# SensorPCB.net
KiCad netlist of a schematic drawn in EAGLE
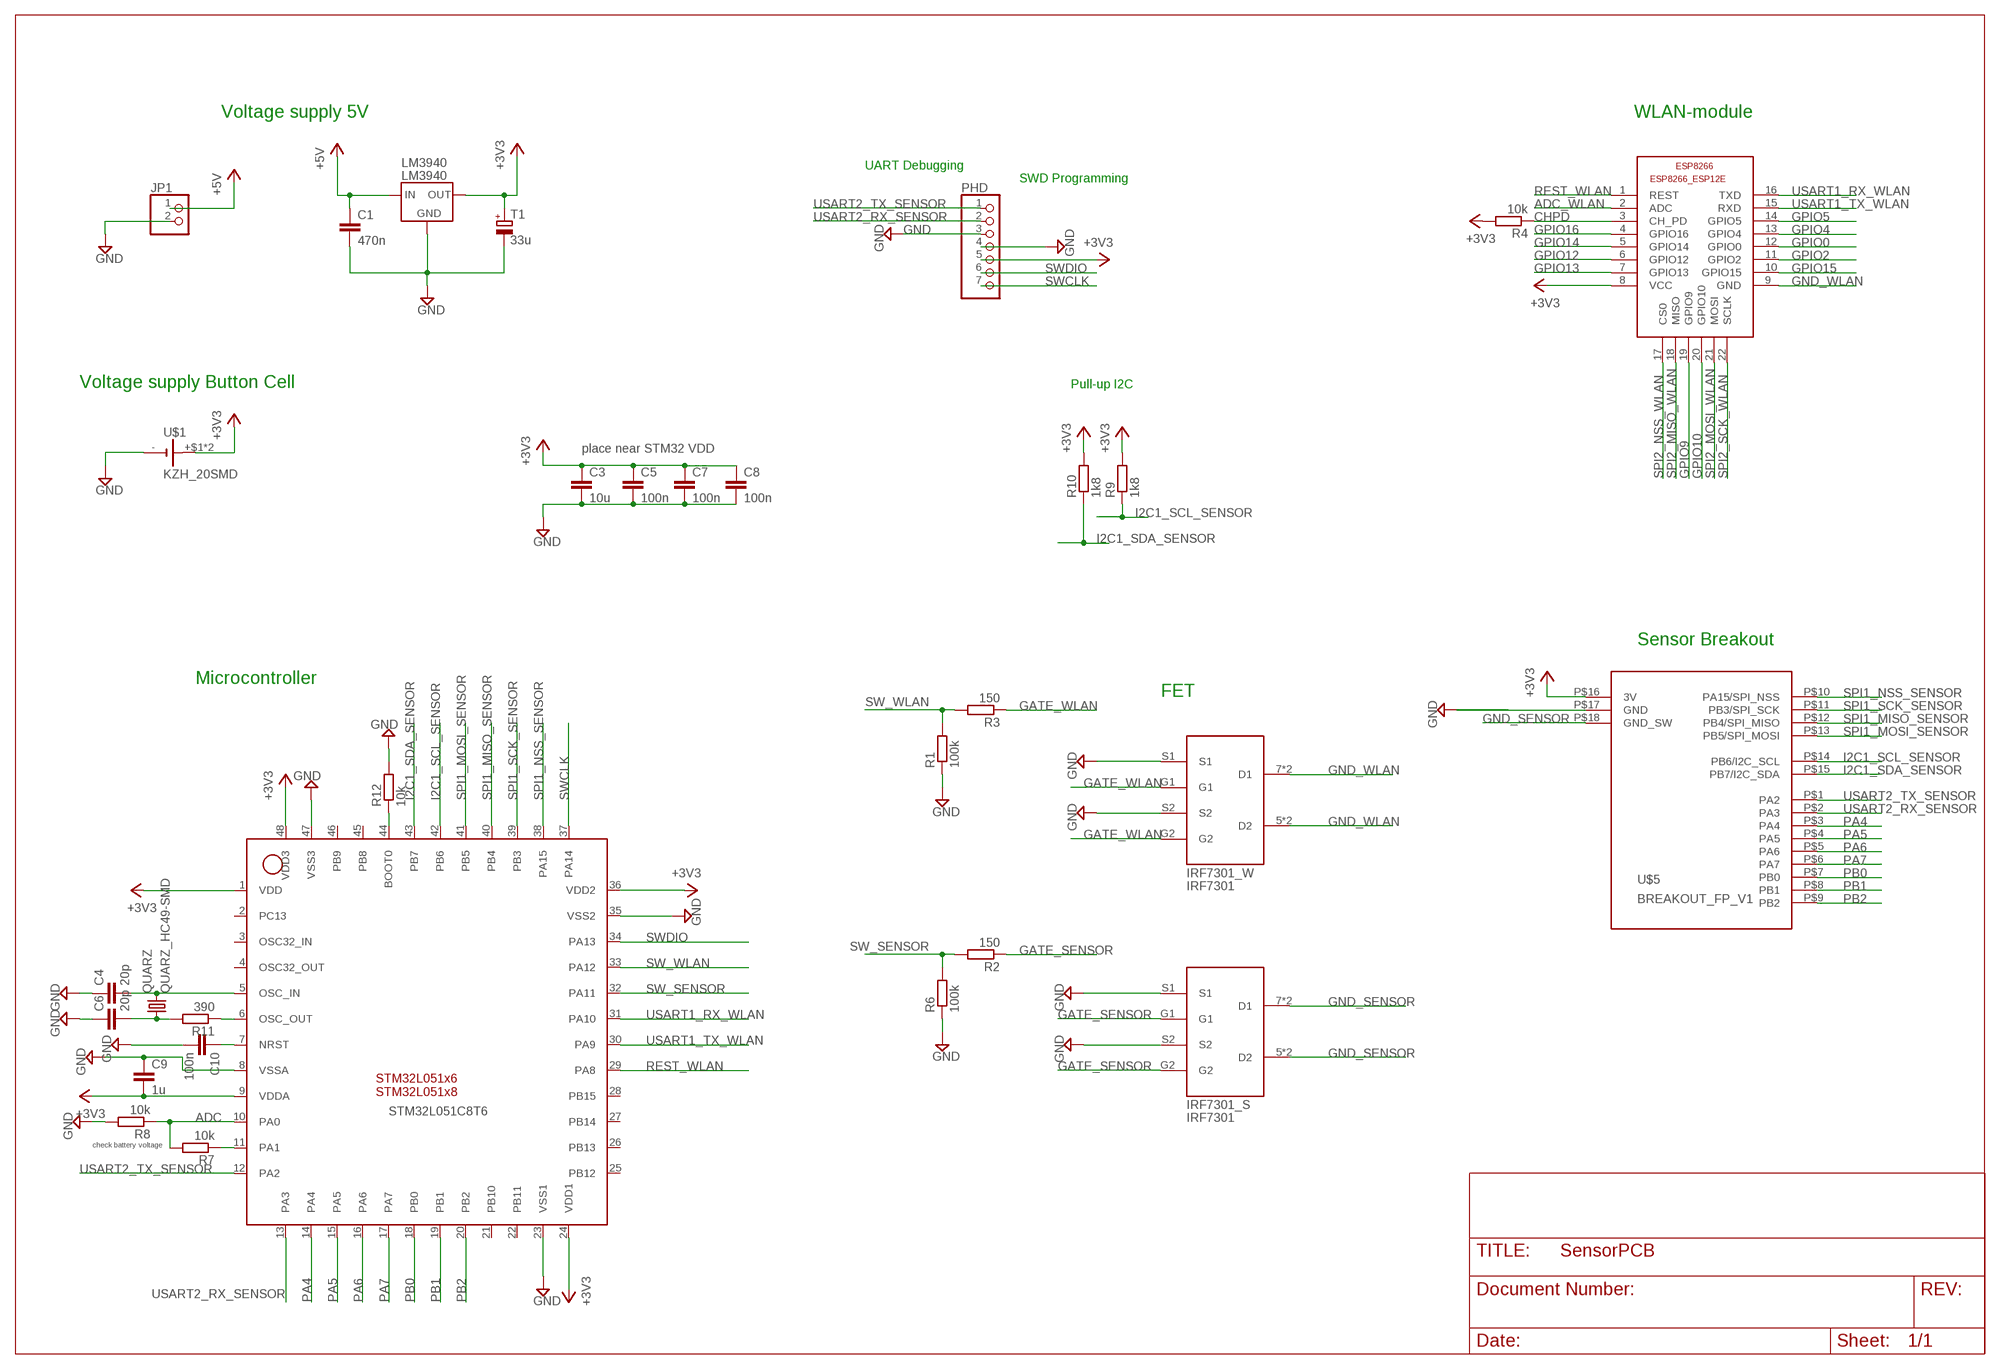
[diagram p0: schematic, sheet 1]

(export (version "E")
  (design (tool "Eeschema 10.0.6"))
  (components
    (comp (ref "C1")
      (value "470n")
      (footprint "eagle-import:C0805")
      (libsource (lib "eagle-import") (part "C-EUC0805"))
    )
    (comp (ref "C3")
      (value "10u")
      (footprint "eagle-import:C0805")
      (libsource (lib "eagle-import") (part "C-EUC0805"))
    )
    (comp (ref "C4")
      (value "20p")
      (footprint "eagle-import:C0805")
      (libsource (lib "eagle-import") (part "C-EUC0805"))
    )
    (comp (ref "C5")
      (value "100n")
      (footprint "eagle-import:C0805")
      (libsource (lib "eagle-import") (part "C-EUC0805"))
    )
    (comp (ref "C6")
      (value "20p")
      (footprint "eagle-import:C0805")
      (libsource (lib "eagle-import") (part "C-EUC0805"))
    )
    (comp (ref "C7")
      (value "100n")
      (footprint "eagle-import:C0805")
      (libsource (lib "eagle-import") (part "C-EUC0805"))
    )
    (comp (ref "C8")
      (value "100n")
      (footprint "eagle-import:C0805")
      (libsource (lib "eagle-import") (part "C-EUC0805"))
    )
    (comp (ref "C9")
      (value "1u")
      (footprint "eagle-import:C0805")
      (libsource (lib "eagle-import") (part "C-EUC0805"))
    )
    (comp (ref "C10")
      (value "100n")
      (footprint "eagle-import:C0805")
      (libsource (lib "eagle-import") (part "C-EUC0805"))
    )
    (comp (ref "ESP8266")
      (value "ESP8266-12EESP8266-ESP12E")
      (footprint "eagle-import:ESP8266-ESP12E")
      (libsource (lib "eagle-import") (part "ESP8266-12EESP8266-ESP12E"))
    )
    (comp (ref "IRF7301_S")
      (value "IRF7301")
      (footprint "eagle-import:IRF7301_PACK_SO8")
      (libsource (lib "eagle-import") (part "IRF7301"))
    )
    (comp (ref "IRF7301_W")
      (value "IRF7301")
      (footprint "eagle-import:IRF7301_PACK_SO8")
      (libsource (lib "eagle-import") (part "IRF7301"))
    )
    (comp (ref "JP1")
      (value "PINHD-1X2_2.54-SMD")
      (footprint "eagle-import:1X02SMD")
      (libsource (lib "eagle-import") (part "PINHD-1X2_2.54-SMD"))
    )
    (comp (ref "LM3940")
      (value "LM3940")
      (footprint "eagle-import:LM3940_PACK")
      (libsource (lib "eagle-import") (part "LM3940"))
    )
    (comp (ref "PHD")
      (value "PINHD-1X7_2.54-SMD")
      (footprint "eagle-import:1X07SMD")
      (libsource (lib "eagle-import") (part "PINHD-1X7_2.54-SMD"))
    )
    (comp (ref "QUARZ")
      (value "QUARZ_HC49-SMD")
      (footprint "eagle-import:HC49-SMD")
      (libsource (lib "eagle-import") (part "QUARZ_HC49-SMD"))
    )
    (comp (ref "R1")
      (value "100k")
      (footprint "eagle-import:R0805")
      (libsource (lib "eagle-import") (part "R-EU_R0805"))
    )
    (comp (ref "R2")
      (value "150")
      (footprint "eagle-import:R0805")
      (libsource (lib "eagle-import") (part "R-EU_R0805"))
    )
    (comp (ref "R3")
      (value "150")
      (footprint "eagle-import:R0805")
      (libsource (lib "eagle-import") (part "R-EU_R0805"))
    )
    (comp (ref "R4")
      (value "10k")
      (footprint "eagle-import:R0805")
      (libsource (lib "eagle-import") (part "R-EU_R0805"))
    )
    (comp (ref "R6")
      (value "100k")
      (footprint "eagle-import:R0805")
      (libsource (lib "eagle-import") (part "R-EU_R0805"))
    )
    (comp (ref "R7")
      (value "10k")
      (footprint "eagle-import:R0805")
      (libsource (lib "eagle-import") (part "R-EU_R0805"))
    )
    (comp (ref "R8")
      (value "10k")
      (footprint "eagle-import:R0805")
      (libsource (lib "eagle-import") (part "R-EU_R0805"))
    )
    (comp (ref "R9")
      (value "1k8")
      (footprint "eagle-import:R0805")
      (libsource (lib "eagle-import") (part "R-EU_R0805"))
    )
    (comp (ref "R10")
      (value "1k8")
      (footprint "eagle-import:R0805")
      (libsource (lib "eagle-import") (part "R-EU_R0805"))
    )
    (comp (ref "R11")
      (value "390")
      (footprint "eagle-import:R0805")
      (libsource (lib "eagle-import") (part "R-EU_R0805"))
    )
    (comp (ref "R12")
      (value "10k")
      (footprint "eagle-import:R0805")
      (libsource (lib "eagle-import") (part "R-EU_R0805"))
    )
    (comp (ref "STM32L051C8T6")
      (value "STM32L051X6/8")
      (footprint "eagle-import:LQFP48")
      (libsource (lib "eagle-import") (part "STM32L051X6/8"))
    )
    (comp (ref "T1")
      (value "33u")
      (footprint "eagle-import:1206")
      (libsource (lib "eagle-import") (part "CAP_TANTAL_1206"))
    )
    (comp (ref "U$1")
      (value "KZH_20SMD")
      (footprint "eagle-import:KHZ_20SMD")
      (libsource (lib "eagle-import") (part "KZH_20SMD"))
    )
    (comp (ref "U$5")
      (value "BREAKOUT_FP_V1")
      (footprint "eagle-import:BREAKOUT_FOOTPRINT_V1")
      (libsource (lib "eagle-import") (part "BREAKOUT_FP_V1"))
    )
  )
  (nets
    (net (code "1") (name "+3V3") (class "Default")
      (node (ref "C3") (pin "1") (pinfunction "1_1") (pintype "passive"))
      (node (ref "C5") (pin "1") (pinfunction "1_1") (pintype "passive"))
      (node (ref "C7") (pin "1") (pinfunction "1_1") (pintype "passive"))
      (node (ref "C8") (pin "1") (pinfunction "1_1") (pintype "passive"))
      (node (ref "C9") (pin "2") (pinfunction "2_2") (pintype "passive"))
      (node (ref "ESP8266") (pin "8") (pinfunction "VCC_8") (pintype "bidirectional"))
      (node (ref "LM3940") (pin "3") (pinfunction "OUT_3") (pintype "passive"))
      (node (ref "PHD") (pin "5") (pinfunction "5_5") (pintype "passive"))
      (node (ref "R10") (pin "2") (pinfunction "2_2") (pintype "passive"))
      (node (ref "R4") (pin "2") (pinfunction "2_2") (pintype "passive"))
      (node (ref "R9") (pin "2") (pinfunction "2_2") (pintype "passive"))
      (node (ref "STM32L051C8T6") (pin "1") (pinfunction "VDD_1") (pintype "bidirectional"))
      (node (ref "STM32L051C8T6") (pin "24") (pinfunction "VDD1_24") (pintype "bidirectional"))
      (node (ref "STM32L051C8T6") (pin "36") (pinfunction "VDD2_36") (pintype "bidirectional"))
      (node (ref "STM32L051C8T6") (pin "48") (pinfunction "VDD3_48") (pintype "bidirectional"))
      (node (ref "STM32L051C8T6") (pin "9") (pinfunction "VDDA_9") (pintype "input"))
      (node (ref "T1") (pin "1") (pinfunction "+_1") (pintype "passive"))
      (node (ref "U$1") (pin "+$1") (pinfunction "+_+$1") (pintype "passive"))
      (node (ref "U$1") (pin "+$2") (pinfunction "+_+$2") (pintype "passive"))
      (node (ref "U$5") (pin "P$16") (pinfunction "3V_P$16") (pintype "bidirectional"))
    )
    (net (code "2") (name "+5V") (class "Default")
      (node (ref "C1") (pin "1") (pinfunction "1_1") (pintype "passive"))
      (node (ref "JP1") (pin "1") (pinfunction "1_1") (pintype "passive"))
      (node (ref "LM3940") (pin "1") (pinfunction "IN_1") (pintype "input"))
    )
    (net (code "3") (name "/ADC") (class "Default")
      (node (ref "R7") (pin "2") (pinfunction "2_2") (pintype "passive"))
      (node (ref "R8") (pin "1") (pinfunction "1_1") (pintype "passive"))
      (node (ref "STM32L051C8T6") (pin "10") (pinfunction "PA0_10") (pintype "passive"))
    )
    (net (code "4") (name "/ADC_WLAN") (class "Default")
      (node (ref "ESP8266") (pin "2") (pinfunction "ADC_2") (pintype "bidirectional"))
    )
    (net (code "5") (name "/CHPD") (class "Default")
      (node (ref "ESP8266") (pin "3") (pinfunction "CH_PD_3") (pintype "bidirectional"))
      (node (ref "R4") (pin "1") (pinfunction "1_1") (pintype "passive"))
    )
    (net (code "6") (name "/GATE_SENSOR") (class "Default")
      (node (ref "IRF7301_S") (pin "G1") (pinfunction "G1_G1") (pintype "bidirectional"))
      (node (ref "IRF7301_S") (pin "G2") (pinfunction "G2_G2") (pintype "bidirectional"))
      (node (ref "R2") (pin "1") (pinfunction "1_1") (pintype "passive"))
    )
    (net (code "7") (name "/GATE_WLAN") (class "Default")
      (node (ref "IRF7301_W") (pin "G1") (pinfunction "G1_G1") (pintype "bidirectional"))
      (node (ref "IRF7301_W") (pin "G2") (pinfunction "G2_G2") (pintype "bidirectional"))
      (node (ref "R3") (pin "1") (pinfunction "1_1") (pintype "passive"))
    )
    (net (code "8") (name "/GND_SENSOR") (class "Default")
      (node (ref "IRF7301_S") (pin "5") (pinfunction "D2_5") (pintype "bidirectional"))
      (node (ref "IRF7301_S") (pin "7") (pinfunction "D1_7") (pintype "bidirectional"))
      (node (ref "IRF7301_S") (pin "D1") (pinfunction "D1_D1") (pintype "bidirectional"))
      (node (ref "IRF7301_S") (pin "D2") (pinfunction "D2_D2") (pintype "bidirectional"))
      (node (ref "U$5") (pin "P$18") (pinfunction "GND_SW_P$18") (pintype "bidirectional"))
    )
    (net (code "9") (name "/GND_WLAN") (class "Default")
      (node (ref "ESP8266") (pin "9") (pinfunction "GND_9") (pintype "bidirectional"))
      (node (ref "IRF7301_W") (pin "5") (pinfunction "D2_5") (pintype "bidirectional"))
      (node (ref "IRF7301_W") (pin "7") (pinfunction "D1_7") (pintype "bidirectional"))
      (node (ref "IRF7301_W") (pin "D1") (pinfunction "D1_D1") (pintype "bidirectional"))
      (node (ref "IRF7301_W") (pin "D2") (pinfunction "D2_D2") (pintype "bidirectional"))
    )
    (net (code "10") (name "/GPIO0") (class "Default")
      (node (ref "ESP8266") (pin "12") (pinfunction "GPIO0_12") (pintype "bidirectional"))
    )
    (net (code "11") (name "/GPIO2") (class "Default")
      (node (ref "ESP8266") (pin "11") (pinfunction "GPIO2_11") (pintype "bidirectional"))
    )
    (net (code "12") (name "/GPIO4") (class "Default")
      (node (ref "ESP8266") (pin "13") (pinfunction "GPIO4_13") (pintype "bidirectional"))
    )
    (net (code "13") (name "/GPIO5") (class "Default")
      (node (ref "ESP8266") (pin "14") (pinfunction "GPIO5_14") (pintype "bidirectional"))
    )
    (net (code "14") (name "/GPIO9") (class "Default")
      (node (ref "ESP8266") (pin "19") (pinfunction "GPIO9_19") (pintype "bidirectional"))
    )
    (net (code "15") (name "/GPIO10") (class "Default")
      (node (ref "ESP8266") (pin "20") (pinfunction "GPIO10_20") (pintype "bidirectional"))
    )
    (net (code "16") (name "/GPIO12") (class "Default")
      (node (ref "ESP8266") (pin "6") (pinfunction "GPIO12_6") (pintype "bidirectional"))
    )
    (net (code "17") (name "/GPIO13") (class "Default")
      (node (ref "ESP8266") (pin "7") (pinfunction "GPIO13_7") (pintype "bidirectional"))
    )
    (net (code "18") (name "/GPIO14") (class "Default")
      (node (ref "ESP8266") (pin "5") (pinfunction "GPIO14_5") (pintype "bidirectional"))
    )
    (net (code "19") (name "/GPIO15") (class "Default")
      (node (ref "ESP8266") (pin "10") (pinfunction "GPIO15_10") (pintype "bidirectional"))
    )
    (net (code "20") (name "/GPIO16") (class "Default")
      (node (ref "ESP8266") (pin "4") (pinfunction "GPIO16_4") (pintype "bidirectional"))
    )
    (net (code "21") (name "/I2C1_SCL_SENSOR") (class "Default")
      (node (ref "R9") (pin "1") (pinfunction "1_1") (pintype "passive"))
      (node (ref "STM32L051C8T6") (pin "42") (pinfunction "PB6_42") (pintype "bidirectional"))
      (node (ref "U$5") (pin "P$14") (pinfunction "PB6/I2C_SCL_P$14") (pintype "bidirectional"))
    )
    (net (code "22") (name "/I2C1_SDA_SENSOR") (class "Default")
      (node (ref "R10") (pin "1") (pinfunction "1_1") (pintype "passive"))
      (node (ref "STM32L051C8T6") (pin "43") (pinfunction "PB7_43") (pintype "bidirectional"))
      (node (ref "U$5") (pin "P$15") (pinfunction "PB7/I2C_SDA_P$15") (pintype "bidirectional"))
    )
    (net (code "23") (name "/PA4") (class "Default")
      (node (ref "STM32L051C8T6") (pin "14") (pinfunction "PA4_14") (pintype "bidirectional"))
      (node (ref "U$5") (pin "P$3") (pinfunction "PA4_P$3") (pintype "bidirectional"))
    )
    (net (code "24") (name "/PA5") (class "Default")
      (node (ref "STM32L051C8T6") (pin "15") (pinfunction "PA5_15") (pintype "bidirectional"))
      (node (ref "U$5") (pin "P$4") (pinfunction "PA5_P$4") (pintype "bidirectional"))
    )
    (net (code "25") (name "/PA6") (class "Default")
      (node (ref "STM32L051C8T6") (pin "16") (pinfunction "PA6_16") (pintype "bidirectional"))
      (node (ref "U$5") (pin "P$5") (pinfunction "PA6_P$5") (pintype "bidirectional"))
    )
    (net (code "26") (name "/PA7") (class "Default")
      (node (ref "STM32L051C8T6") (pin "17") (pinfunction "PA7_17") (pintype "bidirectional"))
      (node (ref "U$5") (pin "P$6") (pinfunction "PA7_P$6") (pintype "bidirectional"))
    )
    (net (code "27") (name "/PB0") (class "Default")
      (node (ref "STM32L051C8T6") (pin "18") (pinfunction "PB0_18") (pintype "bidirectional"))
      (node (ref "U$5") (pin "P$7") (pinfunction "PB0_P$7") (pintype "bidirectional"))
    )
    (net (code "28") (name "/PB1") (class "Default")
      (node (ref "STM32L051C8T6") (pin "19") (pinfunction "PB1_19") (pintype "bidirectional"))
      (node (ref "U$5") (pin "P$8") (pinfunction "PB1_P$8") (pintype "bidirectional"))
    )
    (net (code "29") (name "/PB2") (class "Default")
      (node (ref "STM32L051C8T6") (pin "20") (pinfunction "PB2_20") (pintype "bidirectional"))
      (node (ref "U$5") (pin "P$9") (pinfunction "PB2_P$9") (pintype "bidirectional"))
    )
    (net (code "30") (name "/REST_WLAN") (class "Default")
      (node (ref "ESP8266") (pin "1") (pinfunction "REST_1") (pintype "bidirectional"))
      (node (ref "STM32L051C8T6") (pin "29") (pinfunction "PA8_29") (pintype "bidirectional"))
    )
    (net (code "31") (name "/SPI1_MISO_SENSOR") (class "Default")
      (node (ref "STM32L051C8T6") (pin "40") (pinfunction "PB4_40") (pintype "bidirectional"))
      (node (ref "U$5") (pin "P$12") (pinfunction "PB4/SPI_MISO_P$12") (pintype "bidirectional"))
    )
    (net (code "32") (name "/SPI1_MOSI_SENSOR") (class "Default")
      (node (ref "STM32L051C8T6") (pin "41") (pinfunction "PB5_41") (pintype "bidirectional"))
      (node (ref "U$5") (pin "P$13") (pinfunction "PB5/SPI_MOSI_P$13") (pintype "bidirectional"))
    )
    (net (code "33") (name "/SPI1_NSS_SENSOR") (class "Default")
      (node (ref "STM32L051C8T6") (pin "38") (pinfunction "PA15_38") (pintype "bidirectional"))
      (node (ref "U$5") (pin "P$10") (pinfunction "PA15/SPI_NSS_P$10") (pintype "bidirectional"))
    )
    (net (code "34") (name "/SPI1_SCK_SENSOR") (class "Default")
      (node (ref "STM32L051C8T6") (pin "39") (pinfunction "PB3_39") (pintype "bidirectional"))
      (node (ref "U$5") (pin "P$11") (pinfunction "PB3/SPI_SCK_P$11") (pintype "bidirectional"))
    )
    (net (code "35") (name "/SPI2_MISO_WLAN") (class "Default")
      (node (ref "ESP8266") (pin "18") (pinfunction "MISO_18") (pintype "bidirectional"))
    )
    (net (code "36") (name "/SPI2_MOSI_WLAN") (class "Default")
      (node (ref "ESP8266") (pin "21") (pinfunction "MOSI_21") (pintype "bidirectional"))
    )
    (net (code "37") (name "/SPI2_NSS_WLAN") (class "Default")
      (node (ref "ESP8266") (pin "17") (pinfunction "CS0_17") (pintype "bidirectional"))
    )
    (net (code "38") (name "/SPI2_SCK_WLAN") (class "Default")
      (node (ref "ESP8266") (pin "22") (pinfunction "SCLK_22") (pintype "bidirectional"))
    )
    (net (code "39") (name "/SWCLK") (class "Default")
      (node (ref "PHD") (pin "7") (pinfunction "7_7") (pintype "passive"))
      (node (ref "STM32L051C8T6") (pin "37") (pinfunction "PA14_37") (pintype "bidirectional"))
    )
    (net (code "40") (name "/SWDIO") (class "Default")
      (node (ref "PHD") (pin "6") (pinfunction "6_6") (pintype "passive"))
      (node (ref "STM32L051C8T6") (pin "34") (pinfunction "PA13_34") (pintype "bidirectional"))
    )
    (net (code "41") (name "/SW_SENSOR") (class "Default")
      (node (ref "R2") (pin "2") (pinfunction "2_2") (pintype "passive"))
      (node (ref "R6") (pin "2") (pinfunction "2_2") (pintype "passive"))
      (node (ref "STM32L051C8T6") (pin "32") (pinfunction "PA11_32") (pintype "bidirectional"))
    )
    (net (code "42") (name "/SW_WLAN") (class "Default")
      (node (ref "R1") (pin "2") (pinfunction "2_2") (pintype "passive"))
      (node (ref "R3") (pin "2") (pinfunction "2_2") (pintype "passive"))
      (node (ref "STM32L051C8T6") (pin "33") (pinfunction "PA12_33") (pintype "bidirectional"))
    )
    (net (code "43") (name "/USART1_RX_WLAN") (class "Default")
      (node (ref "ESP8266") (pin "16") (pinfunction "TXD_16") (pintype "bidirectional"))
      (node (ref "STM32L051C8T6") (pin "31") (pinfunction "PA10_31") (pintype "bidirectional"))
    )
    (net (code "44") (name "/USART1_TX_WLAN") (class "Default")
      (node (ref "ESP8266") (pin "15") (pinfunction "RXD_15") (pintype "bidirectional"))
      (node (ref "STM32L051C8T6") (pin "30") (pinfunction "PA9_30") (pintype "bidirectional"))
    )
    (net (code "45") (name "/USART2_RX_SENSOR") (class "Default")
      (node (ref "PHD") (pin "2") (pinfunction "2_2") (pintype "passive"))
      (node (ref "STM32L051C8T6") (pin "13") (pinfunction "PA3_13") (pintype "bidirectional"))
      (node (ref "U$5") (pin "P$2") (pinfunction "PA3_P$2") (pintype "bidirectional"))
    )
    (net (code "46") (name "/USART2_TX_SENSOR") (class "Default")
      (node (ref "PHD") (pin "1") (pinfunction "1_1") (pintype "passive"))
      (node (ref "STM32L051C8T6") (pin "12") (pinfunction "PA2_12") (pintype "power_in"))
      (node (ref "U$5") (pin "P$1") (pinfunction "PA2_P$1") (pintype "bidirectional"))
    )
    (net (code "47") (name "GND") (class "Default")
      (node (ref "C1") (pin "2") (pinfunction "2_2") (pintype "passive"))
      (node (ref "C10") (pin "2") (pinfunction "2_2") (pintype "passive"))
      (node (ref "C3") (pin "2") (pinfunction "2_2") (pintype "passive"))
      (node (ref "C4") (pin "1") (pinfunction "1_1") (pintype "passive"))
      (node (ref "C5") (pin "2") (pinfunction "2_2") (pintype "passive"))
      (node (ref "C6") (pin "1") (pinfunction "1_1") (pintype "passive"))
      (node (ref "C7") (pin "2") (pinfunction "2_2") (pintype "passive"))
      (node (ref "C8") (pin "2") (pinfunction "2_2") (pintype "passive"))
      (node (ref "C9") (pin "1") (pinfunction "1_1") (pintype "passive"))
      (node (ref "IRF7301_S") (pin "S1") (pinfunction "S1_S1") (pintype "bidirectional"))
      (node (ref "IRF7301_S") (pin "S2") (pinfunction "S2_S2") (pintype "bidirectional"))
      (node (ref "IRF7301_W") (pin "S1") (pinfunction "S1_S1") (pintype "bidirectional"))
      (node (ref "IRF7301_W") (pin "S2") (pinfunction "S2_S2") (pintype "bidirectional"))
      (node (ref "JP1") (pin "2") (pinfunction "2_2") (pintype "passive"))
      (node (ref "LM3940") (pin "2") (pinfunction "GND_2") (pintype "input"))
      (node (ref "LM3940") (pin "4") (pinfunction "GND_4") (pintype "input"))
      (node (ref "PHD") (pin "3") (pinfunction "3_3") (pintype "passive"))
      (node (ref "PHD") (pin "4") (pinfunction "4_4") (pintype "passive"))
      (node (ref "R1") (pin "1") (pinfunction "1_1") (pintype "passive"))
      (node (ref "R12") (pin "2") (pinfunction "2_2") (pintype "passive"))
      (node (ref "R6") (pin "1") (pinfunction "1_1") (pintype "passive"))
      (node (ref "R8") (pin "2") (pinfunction "2_2") (pintype "passive"))
      (node (ref "STM32L051C8T6") (pin "23") (pinfunction "VSS1_23") (pintype "bidirectional"))
      (node (ref "STM32L051C8T6") (pin "35") (pinfunction "VSS2_35") (pintype "bidirectional"))
      (node (ref "STM32L051C8T6") (pin "47") (pinfunction "VSS3_47") (pintype "bidirectional"))
      (node (ref "STM32L051C8T6") (pin "8") (pinfunction "VSSA_8") (pintype "input"))
      (node (ref "T1") (pin "2") (pinfunction "-_2") (pintype "passive"))
      (node (ref "U$1") (pin "-") (pinfunction "-_-") (pintype "passive"))
      (node (ref "U$5") (pin "P$17") (pinfunction "GND_P$17") (pintype "bidirectional"))
    )
    (net (code "48") (name "Net-(C6-Pad2)") (class "Default")
      (node (ref "C6") (pin "2") (pinfunction "2_2") (pintype "passive"))
      (node (ref "QUARZ") (pin "1") (pinfunction "1_1") (pintype "passive"))
      (node (ref "R11") (pin "2") (pinfunction "2_2") (pintype "passive"))
    )
    (net (code "49") (name "Net-(STM32L051C8T6-BOOT0)") (class "Default")
      (node (ref "R12") (pin "1") (pinfunction "1_1") (pintype "passive"))
      (node (ref "STM32L051C8T6") (pin "44") (pinfunction "BOOT0_44") (pintype "bidirectional"))
    )
    (net (code "50") (name "Net-(STM32L051C8T6-NRST)") (class "Default")
      (node (ref "C10") (pin "1") (pinfunction "1_1") (pintype "passive"))
      (node (ref "STM32L051C8T6") (pin "7") (pinfunction "NRST_7") (pintype "input"))
    )
    (net (code "51") (name "Net-(STM32L051C8T6-OSC_IN)") (class "Default")
      (node (ref "C4") (pin "2") (pinfunction "2_2") (pintype "passive"))
      (node (ref "QUARZ") (pin "2") (pinfunction "2_2") (pintype "passive"))
      (node (ref "STM32L051C8T6") (pin "5") (pinfunction "OSC_IN_5") (pintype "input"))
    )
    (net (code "52") (name "Net-(STM32L051C8T6-OSC_OUT)") (class "Default")
      (node (ref "R11") (pin "1") (pinfunction "1_1") (pintype "passive"))
      (node (ref "STM32L051C8T6") (pin "6") (pinfunction "OSC_OUT_6") (pintype "input"))
    )
    (net (code "53") (name "Net-(STM32L051C8T6-PA1)") (class "Default")
      (node (ref "R7") (pin "1") (pinfunction "1_1") (pintype "passive"))
      (node (ref "STM32L051C8T6") (pin "11") (pinfunction "PA1_11") (pintype "power_in"))
    )
    (net (code "54") (name "unconnected-(STM32L051C8T6-OSC32_IN-Pad3)") (class "Default")
      (node (ref "STM32L051C8T6") (pin "3") (pinfunction "OSC32_IN_3") (pintype "bidirectional"))
    )
    (net (code "55") (name "unconnected-(STM32L051C8T6-OSC32_OUT-Pad4)") (class "Default")
      (node (ref "STM32L051C8T6") (pin "4") (pinfunction "OSC32_OUT_4") (pintype "input"))
    )
    (net (code "56") (name "unconnected-(STM32L051C8T6-PB8-Pad45)") (class "Default")
      (node (ref "STM32L051C8T6") (pin "45") (pinfunction "PB8_45") (pintype "bidirectional"))
    )
    (net (code "57") (name "unconnected-(STM32L051C8T6-PB9-Pad46)") (class "Default")
      (node (ref "STM32L051C8T6") (pin "46") (pinfunction "PB9_46") (pintype "bidirectional"))
    )
    (net (code "58") (name "unconnected-(STM32L051C8T6-PB10-Pad21)") (class "Default")
      (node (ref "STM32L051C8T6") (pin "21") (pinfunction "PB10_21") (pintype "bidirectional"))
    )
    (net (code "59") (name "unconnected-(STM32L051C8T6-PB11-Pad22)") (class "Default")
      (node (ref "STM32L051C8T6") (pin "22") (pinfunction "PB11_22") (pintype "bidirectional"))
    )
    (net (code "60") (name "unconnected-(STM32L051C8T6-PB12-Pad25)") (class "Default")
      (node (ref "STM32L051C8T6") (pin "25") (pinfunction "PB12_25") (pintype "bidirectional"))
    )
    (net (code "61") (name "unconnected-(STM32L051C8T6-PB13-Pad26)") (class "Default")
      (node (ref "STM32L051C8T6") (pin "26") (pinfunction "PB13_26") (pintype "bidirectional"))
    )
    (net (code "62") (name "unconnected-(STM32L051C8T6-PB14-Pad27)") (class "Default")
      (node (ref "STM32L051C8T6") (pin "27") (pinfunction "PB14_27") (pintype "bidirectional"))
    )
    (net (code "63") (name "unconnected-(STM32L051C8T6-PB15-Pad28)") (class "Default")
      (node (ref "STM32L051C8T6") (pin "28") (pinfunction "PB15_28") (pintype "bidirectional"))
    )
    (net (code "64") (name "unconnected-(STM32L051C8T6-PC13-Pad2)") (class "Default")
      (node (ref "STM32L051C8T6") (pin "2") (pinfunction "PC13_2") (pintype "bidirectional"))
    )
  )
)
